# connector-top-j4-0.net
KiCad netlist of a schematic drawn in Altium Designer
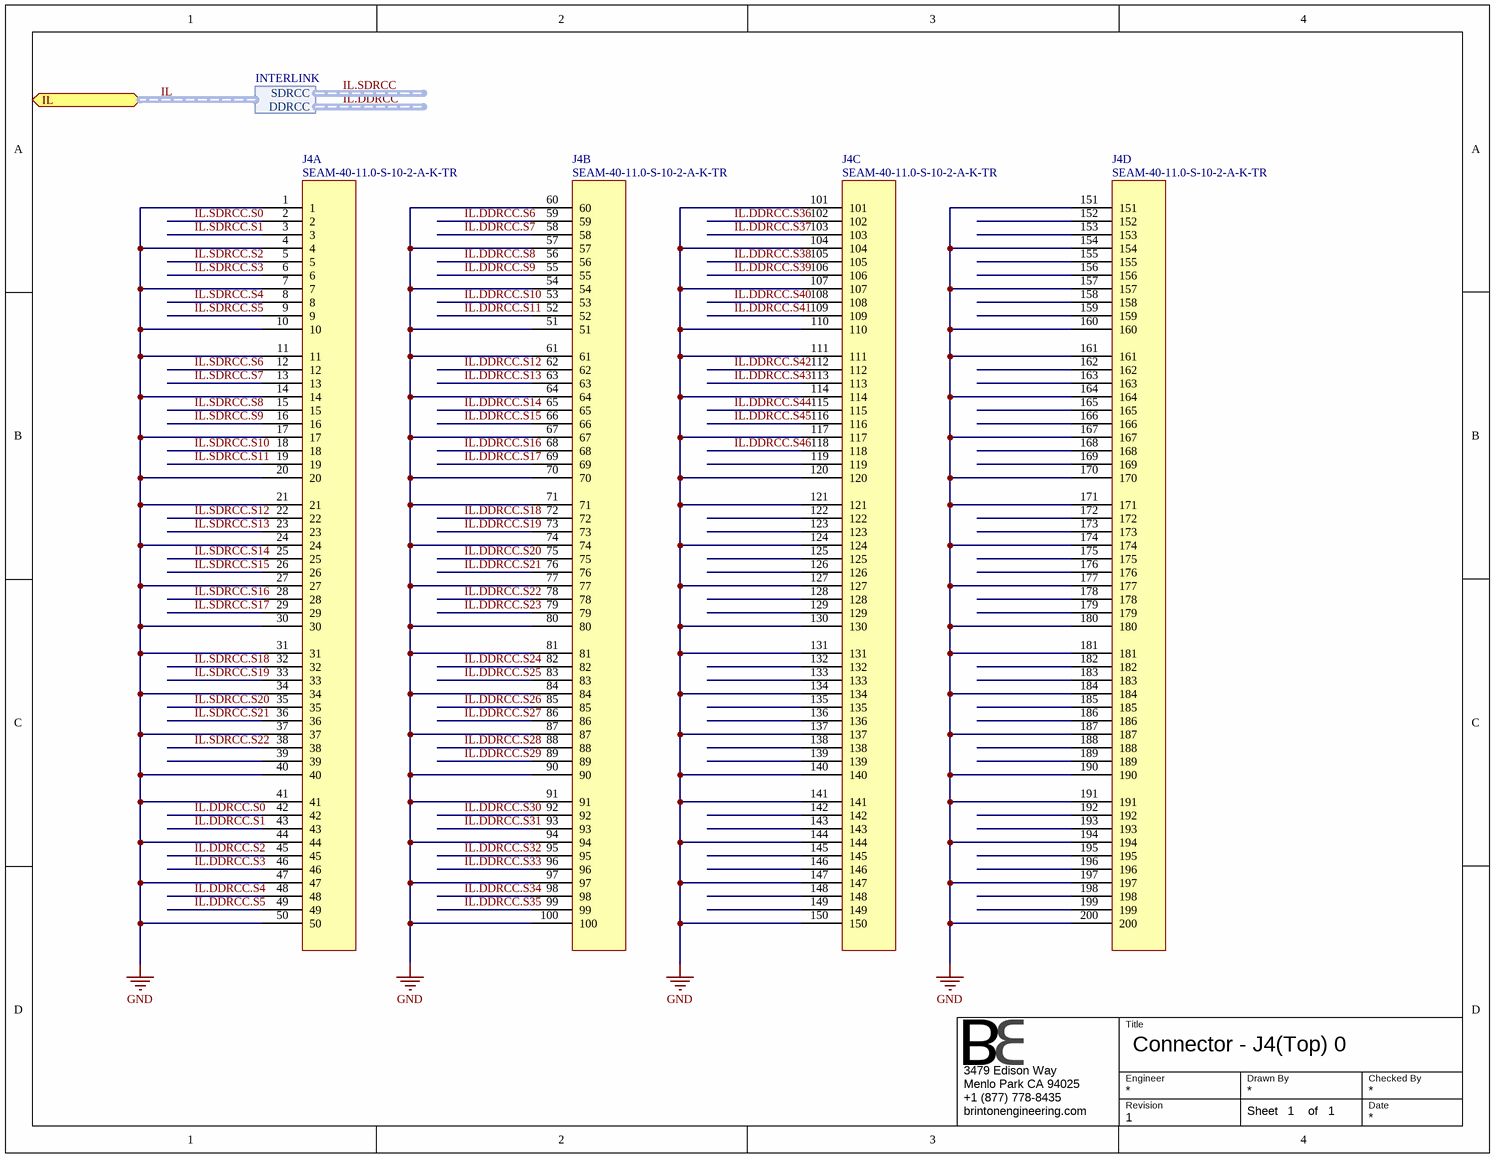
[diagram p0: connector-top-j4-0.SchDoc]

(export (version "E")
  (design (tool "Eeschema 10.0.6"))
  (components
    (comp (ref "J4")
      (value "SEAM-40-11.0-S-10-2-A-K-TR")
      (footprint "samtec:SEAM-40-11.0-S-10-2-A-K-TR")
      (description "Terminal Array Assembly, Surface Mount, 0.050\" Pitch, 400 Pins")
      (fields (field (name "MANUFACTURER") "Samtec"))
      (libsource (lib "samtec") (part "SEAM-40-11.0-S-10-2-A-K-TR"))
    )
  )
  (nets
    (net (code "3") (name "/IL.DDRCC.S0") (class "Default")
      (node (ref "J4") (pin "42") (pinfunction "42_42") (pintype "passive"))
    )
    (net (code "4") (name "/IL.DDRCC.S1") (class "Default")
      (node (ref "J4") (pin "43") (pinfunction "43_43") (pintype "passive"))
    )
    (net (code "5") (name "/IL.DDRCC.S2") (class "Default")
      (node (ref "J4") (pin "45") (pinfunction "45_45") (pintype "passive"))
    )
    (net (code "6") (name "/IL.DDRCC.S3") (class "Default")
      (node (ref "J4") (pin "46") (pinfunction "46_46") (pintype "passive"))
    )
    (net (code "7") (name "/IL.DDRCC.S4") (class "Default")
      (node (ref "J4") (pin "48") (pinfunction "48_48") (pintype "passive"))
    )
    (net (code "8") (name "/IL.DDRCC.S5") (class "Default")
      (node (ref "J4") (pin "49") (pinfunction "49_49") (pintype "passive"))
    )
    (net (code "9") (name "/IL.DDRCC.S6") (class "Default")
      (node (ref "J4") (pin "59") (pinfunction "59_59") (pintype "passive"))
    )
    (net (code "10") (name "/IL.DDRCC.S7") (class "Default")
      (node (ref "J4") (pin "58") (pinfunction "58_58") (pintype "passive"))
    )
    (net (code "11") (name "/IL.DDRCC.S8") (class "Default")
      (node (ref "J4") (pin "56") (pinfunction "56_56") (pintype "passive"))
    )
    (net (code "12") (name "/IL.DDRCC.S9") (class "Default")
      (node (ref "J4") (pin "55") (pinfunction "55_55") (pintype "passive"))
    )
    (net (code "13") (name "/IL.DDRCC.S10") (class "Default")
      (node (ref "J4") (pin "53") (pinfunction "53_53") (pintype "passive"))
    )
    (net (code "14") (name "/IL.DDRCC.S11") (class "Default")
      (node (ref "J4") (pin "52") (pinfunction "52_52") (pintype "passive"))
    )
    (net (code "15") (name "/IL.DDRCC.S12") (class "Default")
      (node (ref "J4") (pin "62") (pinfunction "62_62") (pintype "passive"))
    )
    (net (code "16") (name "/IL.DDRCC.S13") (class "Default")
      (node (ref "J4") (pin "63") (pinfunction "63_63") (pintype "passive"))
    )
    (net (code "17") (name "/IL.DDRCC.S14") (class "Default")
      (node (ref "J4") (pin "65") (pinfunction "65_65") (pintype "passive"))
    )
    (net (code "18") (name "/IL.DDRCC.S15") (class "Default")
      (node (ref "J4") (pin "66") (pinfunction "66_66") (pintype "passive"))
    )
    (net (code "19") (name "/IL.DDRCC.S16") (class "Default")
      (node (ref "J4") (pin "68") (pinfunction "68_68") (pintype "passive"))
    )
    (net (code "20") (name "/IL.DDRCC.S17") (class "Default")
      (node (ref "J4") (pin "69") (pinfunction "69_69") (pintype "passive"))
    )
    (net (code "21") (name "/IL.DDRCC.S18") (class "Default")
      (node (ref "J4") (pin "72") (pinfunction "72_72") (pintype "passive"))
    )
    (net (code "22") (name "/IL.DDRCC.S19") (class "Default")
      (node (ref "J4") (pin "73") (pinfunction "73_73") (pintype "passive"))
    )
    (net (code "23") (name "/IL.DDRCC.S20") (class "Default")
      (node (ref "J4") (pin "75") (pinfunction "75_75") (pintype "passive"))
    )
    (net (code "24") (name "/IL.DDRCC.S21") (class "Default")
      (node (ref "J4") (pin "76") (pinfunction "76_76") (pintype "passive"))
    )
    (net (code "25") (name "/IL.DDRCC.S22") (class "Default")
      (node (ref "J4") (pin "78") (pinfunction "78_78") (pintype "passive"))
    )
    (net (code "26") (name "/IL.DDRCC.S23") (class "Default")
      (node (ref "J4") (pin "79") (pinfunction "79_79") (pintype "passive"))
    )
    (net (code "27") (name "/IL.DDRCC.S24") (class "Default")
      (node (ref "J4") (pin "82") (pinfunction "82_82") (pintype "passive"))
    )
    (net (code "28") (name "/IL.DDRCC.S25") (class "Default")
      (node (ref "J4") (pin "83") (pinfunction "83_83") (pintype "passive"))
    )
    (net (code "29") (name "/IL.DDRCC.S26") (class "Default")
      (node (ref "J4") (pin "85") (pinfunction "85_85") (pintype "passive"))
    )
    (net (code "30") (name "/IL.DDRCC.S27") (class "Default")
      (node (ref "J4") (pin "86") (pinfunction "86_86") (pintype "passive"))
    )
    (net (code "31") (name "/IL.DDRCC.S28") (class "Default")
      (node (ref "J4") (pin "88") (pinfunction "88_88") (pintype "passive"))
    )
    (net (code "32") (name "/IL.DDRCC.S29") (class "Default")
      (node (ref "J4") (pin "89") (pinfunction "89_89") (pintype "passive"))
    )
    (net (code "33") (name "/IL.DDRCC.S30") (class "Default")
      (node (ref "J4") (pin "92") (pinfunction "92_92") (pintype "passive"))
    )
    (net (code "34") (name "/IL.DDRCC.S31") (class "Default")
      (node (ref "J4") (pin "93") (pinfunction "93_93") (pintype "passive"))
    )
    (net (code "35") (name "/IL.DDRCC.S32") (class "Default")
      (node (ref "J4") (pin "95") (pinfunction "95_95") (pintype "passive"))
    )
    (net (code "36") (name "/IL.DDRCC.S33") (class "Default")
      (node (ref "J4") (pin "96") (pinfunction "96_96") (pintype "passive"))
    )
    (net (code "37") (name "/IL.DDRCC.S34") (class "Default")
      (node (ref "J4") (pin "98") (pinfunction "98_98") (pintype "passive"))
    )
    (net (code "38") (name "/IL.DDRCC.S35") (class "Default")
      (node (ref "J4") (pin "99") (pinfunction "99_99") (pintype "passive"))
    )
    (net (code "39") (name "/IL.DDRCC.S36") (class "Default")
      (node (ref "J4") (pin "102") (pinfunction "102_102") (pintype "passive"))
    )
    (net (code "40") (name "/IL.DDRCC.S37") (class "Default")
      (node (ref "J4") (pin "103") (pinfunction "103_103") (pintype "passive"))
    )
    (net (code "41") (name "/IL.DDRCC.S38") (class "Default")
      (node (ref "J4") (pin "105") (pinfunction "105_105") (pintype "passive"))
    )
    (net (code "42") (name "/IL.DDRCC.S39") (class "Default")
      (node (ref "J4") (pin "106") (pinfunction "106_106") (pintype "passive"))
    )
    (net (code "43") (name "/IL.DDRCC.S40") (class "Default")
      (node (ref "J4") (pin "108") (pinfunction "108_108") (pintype "passive"))
    )
    (net (code "44") (name "/IL.DDRCC.S41") (class "Default")
      (node (ref "J4") (pin "109") (pinfunction "109_109") (pintype "passive"))
    )
    (net (code "45") (name "/IL.DDRCC.S42") (class "Default")
      (node (ref "J4") (pin "112") (pinfunction "112_112") (pintype "passive"))
    )
    (net (code "46") (name "/IL.DDRCC.S43") (class "Default")
      (node (ref "J4") (pin "113") (pinfunction "113_113") (pintype "passive"))
    )
    (net (code "47") (name "/IL.DDRCC.S44") (class "Default")
      (node (ref "J4") (pin "115") (pinfunction "115_115") (pintype "passive"))
    )
    (net (code "48") (name "/IL.DDRCC.S45") (class "Default")
      (node (ref "J4") (pin "116") (pinfunction "116_116") (pintype "passive"))
    )
    (net (code "49") (name "/IL.DDRCC.S46") (class "Default")
      (node (ref "J4") (pin "118") (pinfunction "118_118") (pintype "passive"))
    )
    (net (code "51") (name "/IL.SDRCC.S0") (class "Default")
      (node (ref "J4") (pin "2") (pinfunction "2_2") (pintype "passive"))
    )
    (net (code "52") (name "/IL.SDRCC.S1") (class "Default")
      (node (ref "J4") (pin "3") (pinfunction "3_3") (pintype "passive"))
    )
    (net (code "53") (name "/IL.SDRCC.S2") (class "Default")
      (node (ref "J4") (pin "5") (pinfunction "5_5") (pintype "passive"))
    )
    (net (code "54") (name "/IL.SDRCC.S3") (class "Default")
      (node (ref "J4") (pin "6") (pinfunction "6_6") (pintype "passive"))
    )
    (net (code "55") (name "/IL.SDRCC.S4") (class "Default")
      (node (ref "J4") (pin "8") (pinfunction "8_8") (pintype "passive"))
    )
    (net (code "56") (name "/IL.SDRCC.S5") (class "Default")
      (node (ref "J4") (pin "9") (pinfunction "9_9") (pintype "passive"))
    )
    (net (code "57") (name "/IL.SDRCC.S6") (class "Default")
      (node (ref "J4") (pin "12") (pinfunction "12_12") (pintype "passive"))
    )
    (net (code "58") (name "/IL.SDRCC.S7") (class "Default")
      (node (ref "J4") (pin "13") (pinfunction "13_13") (pintype "passive"))
    )
    (net (code "59") (name "/IL.SDRCC.S8") (class "Default")
      (node (ref "J4") (pin "15") (pinfunction "15_15") (pintype "passive"))
    )
    (net (code "60") (name "/IL.SDRCC.S9") (class "Default")
      (node (ref "J4") (pin "16") (pinfunction "16_16") (pintype "passive"))
    )
    (net (code "61") (name "/IL.SDRCC.S10") (class "Default")
      (node (ref "J4") (pin "18") (pinfunction "18_18") (pintype "passive"))
    )
    (net (code "62") (name "/IL.SDRCC.S11") (class "Default")
      (node (ref "J4") (pin "19") (pinfunction "19_19") (pintype "passive"))
    )
    (net (code "63") (name "/IL.SDRCC.S12") (class "Default")
      (node (ref "J4") (pin "22") (pinfunction "22_22") (pintype "passive"))
    )
    (net (code "64") (name "/IL.SDRCC.S13") (class "Default")
      (node (ref "J4") (pin "23") (pinfunction "23_23") (pintype "passive"))
    )
    (net (code "65") (name "/IL.SDRCC.S14") (class "Default")
      (node (ref "J4") (pin "25") (pinfunction "25_25") (pintype "passive"))
    )
    (net (code "66") (name "/IL.SDRCC.S15") (class "Default")
      (node (ref "J4") (pin "26") (pinfunction "26_26") (pintype "passive"))
    )
    (net (code "67") (name "/IL.SDRCC.S16") (class "Default")
      (node (ref "J4") (pin "28") (pinfunction "28_28") (pintype "passive"))
    )
    (net (code "68") (name "/IL.SDRCC.S17") (class "Default")
      (node (ref "J4") (pin "29") (pinfunction "29_29") (pintype "passive"))
    )
    (net (code "69") (name "/IL.SDRCC.S18") (class "Default")
      (node (ref "J4") (pin "32") (pinfunction "32_32") (pintype "passive"))
    )
    (net (code "70") (name "/IL.SDRCC.S19") (class "Default")
      (node (ref "J4") (pin "33") (pinfunction "33_33") (pintype "passive"))
    )
    (net (code "71") (name "/IL.SDRCC.S20") (class "Default")
      (node (ref "J4") (pin "35") (pinfunction "35_35") (pintype "passive"))
    )
    (net (code "72") (name "/IL.SDRCC.S21") (class "Default")
      (node (ref "J4") (pin "36") (pinfunction "36_36") (pintype "passive"))
    )
    (net (code "73") (name "/IL.SDRCC.S22") (class "Default")
      (node (ref "J4") (pin "38") (pinfunction "38_38") (pintype "passive"))
    )
    (net (code "75") (name "GND") (class "Default")
      (node (ref "J4") (pin "1") (pinfunction "1_1") (pintype "passive"))
      (node (ref "J4") (pin "10") (pinfunction "10_10") (pintype "passive"))
      (node (ref "J4") (pin "100") (pinfunction "100_100") (pintype "passive"))
      (node (ref "J4") (pin "101") (pinfunction "101_101") (pintype "passive"))
      (node (ref "J4") (pin "104") (pinfunction "104_104") (pintype "passive"))
      (node (ref "J4") (pin "107") (pinfunction "107_107") (pintype "passive"))
      (node (ref "J4") (pin "11") (pinfunction "11_11") (pintype "passive"))
      (node (ref "J4") (pin "110") (pinfunction "110_110") (pintype "passive"))
      (node (ref "J4") (pin "111") (pinfunction "111_111") (pintype "passive"))
      (node (ref "J4") (pin "114") (pinfunction "114_114") (pintype "passive"))
      (node (ref "J4") (pin "117") (pinfunction "117_117") (pintype "passive"))
      (node (ref "J4") (pin "120") (pinfunction "120_120") (pintype "passive"))
      (node (ref "J4") (pin "121") (pinfunction "121_121") (pintype "passive"))
      (node (ref "J4") (pin "124") (pinfunction "124_124") (pintype "passive"))
      (node (ref "J4") (pin "127") (pinfunction "127_127") (pintype "passive"))
      (node (ref "J4") (pin "130") (pinfunction "130_130") (pintype "passive"))
      (node (ref "J4") (pin "131") (pinfunction "131_131") (pintype "passive"))
      (node (ref "J4") (pin "134") (pinfunction "134_134") (pintype "passive"))
      (node (ref "J4") (pin "137") (pinfunction "137_137") (pintype "passive"))
      (node (ref "J4") (pin "14") (pinfunction "14_14") (pintype "passive"))
      (node (ref "J4") (pin "140") (pinfunction "140_140") (pintype "passive"))
      (node (ref "J4") (pin "141") (pinfunction "141_141") (pintype "passive"))
      (node (ref "J4") (pin "144") (pinfunction "144_144") (pintype "passive"))
      (node (ref "J4") (pin "147") (pinfunction "147_147") (pintype "passive"))
      (node (ref "J4") (pin "150") (pinfunction "150_150") (pintype "passive"))
      (node (ref "J4") (pin "151") (pinfunction "151_151") (pintype "passive"))
      (node (ref "J4") (pin "154") (pinfunction "154_154") (pintype "passive"))
      (node (ref "J4") (pin "157") (pinfunction "157_157") (pintype "passive"))
      (node (ref "J4") (pin "160") (pinfunction "160_160") (pintype "passive"))
      (node (ref "J4") (pin "161") (pinfunction "161_161") (pintype "passive"))
      (node (ref "J4") (pin "164") (pinfunction "164_164") (pintype "passive"))
      (node (ref "J4") (pin "167") (pinfunction "167_167") (pintype "passive"))
      (node (ref "J4") (pin "17") (pinfunction "17_17") (pintype "passive"))
      (node (ref "J4") (pin "170") (pinfunction "170_170") (pintype "passive"))
      (node (ref "J4") (pin "171") (pinfunction "171_171") (pintype "passive"))
      (node (ref "J4") (pin "174") (pinfunction "174_174") (pintype "passive"))
      (node (ref "J4") (pin "177") (pinfunction "177_177") (pintype "passive"))
      (node (ref "J4") (pin "180") (pinfunction "180_180") (pintype "passive"))
      (node (ref "J4") (pin "181") (pinfunction "181_181") (pintype "passive"))
      (node (ref "J4") (pin "184") (pinfunction "184_184") (pintype "passive"))
      (node (ref "J4") (pin "187") (pinfunction "187_187") (pintype "passive"))
      (node (ref "J4") (pin "190") (pinfunction "190_190") (pintype "passive"))
      (node (ref "J4") (pin "191") (pinfunction "191_191") (pintype "passive"))
      (node (ref "J4") (pin "194") (pinfunction "194_194") (pintype "passive"))
      (node (ref "J4") (pin "197") (pinfunction "197_197") (pintype "passive"))
      (node (ref "J4") (pin "20") (pinfunction "20_20") (pintype "passive"))
      (node (ref "J4") (pin "200") (pinfunction "200_200") (pintype "passive"))
      (node (ref "J4") (pin "21") (pinfunction "21_21") (pintype "passive"))
      (node (ref "J4") (pin "24") (pinfunction "24_24") (pintype "passive"))
      (node (ref "J4") (pin "27") (pinfunction "27_27") (pintype "passive"))
      (node (ref "J4") (pin "30") (pinfunction "30_30") (pintype "passive"))
      (node (ref "J4") (pin "31") (pinfunction "31_31") (pintype "passive"))
      (node (ref "J4") (pin "34") (pinfunction "34_34") (pintype "passive"))
      (node (ref "J4") (pin "37") (pinfunction "37_37") (pintype "passive"))
      (node (ref "J4") (pin "4") (pinfunction "4_4") (pintype "passive"))
      (node (ref "J4") (pin "40") (pinfunction "40_40") (pintype "passive"))
      (node (ref "J4") (pin "41") (pinfunction "41_41") (pintype "passive"))
      (node (ref "J4") (pin "44") (pinfunction "44_44") (pintype "passive"))
      (node (ref "J4") (pin "47") (pinfunction "47_47") (pintype "passive"))
      (node (ref "J4") (pin "50") (pinfunction "50_50") (pintype "passive"))
      (node (ref "J4") (pin "51") (pinfunction "51_51") (pintype "passive"))
      (node (ref "J4") (pin "54") (pinfunction "54_54") (pintype "passive"))
      (node (ref "J4") (pin "57") (pinfunction "57_57") (pintype "passive"))
      (node (ref "J4") (pin "60") (pinfunction "60_60") (pintype "passive"))
      (node (ref "J4") (pin "61") (pinfunction "61_61") (pintype "passive"))
      (node (ref "J4") (pin "64") (pinfunction "64_64") (pintype "passive"))
      (node (ref "J4") (pin "67") (pinfunction "67_67") (pintype "passive"))
      (node (ref "J4") (pin "7") (pinfunction "7_7") (pintype "passive"))
      (node (ref "J4") (pin "70") (pinfunction "70_70") (pintype "passive"))
      (node (ref "J4") (pin "71") (pinfunction "71_71") (pintype "passive"))
      (node (ref "J4") (pin "74") (pinfunction "74_74") (pintype "passive"))
      (node (ref "J4") (pin "77") (pinfunction "77_77") (pintype "passive"))
      (node (ref "J4") (pin "80") (pinfunction "80_80") (pintype "passive"))
      (node (ref "J4") (pin "81") (pinfunction "81_81") (pintype "passive"))
      (node (ref "J4") (pin "84") (pinfunction "84_84") (pintype "passive"))
      (node (ref "J4") (pin "87") (pinfunction "87_87") (pintype "passive"))
      (node (ref "J4") (pin "90") (pinfunction "90_90") (pintype "passive"))
      (node (ref "J4") (pin "91") (pinfunction "91_91") (pintype "passive"))
      (node (ref "J4") (pin "94") (pinfunction "94_94") (pintype "passive"))
      (node (ref "J4") (pin "97") (pinfunction "97_97") (pintype "passive"))
    )
    (net (code "76") (name "unconnected-(J4-Pad39)") (class "Default")
      (node (ref "J4") (pin "39") (pinfunction "39_39") (pintype "passive"))
    )
    (net (code "77") (name "unconnected-(J4-Pad119)") (class "Default")
      (node (ref "J4") (pin "119") (pinfunction "119_119") (pintype "passive"))
    )
    (net (code "78") (name "unconnected-(J4-Pad122)") (class "Default")
      (node (ref "J4") (pin "122") (pinfunction "122_122") (pintype "passive"))
    )
    (net (code "79") (name "unconnected-(J4-Pad123)") (class "Default")
      (node (ref "J4") (pin "123") (pinfunction "123_123") (pintype "passive"))
    )
    (net (code "80") (name "unconnected-(J4-Pad125)") (class "Default")
      (node (ref "J4") (pin "125") (pinfunction "125_125") (pintype "passive"))
    )
    (net (code "81") (name "unconnected-(J4-Pad126)") (class "Default")
      (node (ref "J4") (pin "126") (pinfunction "126_126") (pintype "passive"))
    )
    (net (code "82") (name "unconnected-(J4-Pad128)") (class "Default")
      (node (ref "J4") (pin "128") (pinfunction "128_128") (pintype "passive"))
    )
    (net (code "83") (name "unconnected-(J4-Pad129)") (class "Default")
      (node (ref "J4") (pin "129") (pinfunction "129_129") (pintype "passive"))
    )
    (net (code "84") (name "unconnected-(J4-Pad132)") (class "Default")
      (node (ref "J4") (pin "132") (pinfunction "132_132") (pintype "passive"))
    )
    (net (code "85") (name "unconnected-(J4-Pad133)") (class "Default")
      (node (ref "J4") (pin "133") (pinfunction "133_133") (pintype "passive"))
    )
    (net (code "86") (name "unconnected-(J4-Pad135)") (class "Default")
      (node (ref "J4") (pin "135") (pinfunction "135_135") (pintype "passive"))
    )
    (net (code "87") (name "unconnected-(J4-Pad136)") (class "Default")
      (node (ref "J4") (pin "136") (pinfunction "136_136") (pintype "passive"))
    )
    (net (code "88") (name "unconnected-(J4-Pad138)") (class "Default")
      (node (ref "J4") (pin "138") (pinfunction "138_138") (pintype "passive"))
    )
    (net (code "89") (name "unconnected-(J4-Pad139)") (class "Default")
      (node (ref "J4") (pin "139") (pinfunction "139_139") (pintype "passive"))
    )
    (net (code "90") (name "unconnected-(J4-Pad142)") (class "Default")
      (node (ref "J4") (pin "142") (pinfunction "142_142") (pintype "passive"))
    )
    (net (code "91") (name "unconnected-(J4-Pad143)") (class "Default")
      (node (ref "J4") (pin "143") (pinfunction "143_143") (pintype "passive"))
    )
    (net (code "92") (name "unconnected-(J4-Pad145)") (class "Default")
      (node (ref "J4") (pin "145") (pinfunction "145_145") (pintype "passive"))
    )
    (net (code "93") (name "unconnected-(J4-Pad146)") (class "Default")
      (node (ref "J4") (pin "146") (pinfunction "146_146") (pintype "passive"))
    )
    (net (code "94") (name "unconnected-(J4-Pad148)") (class "Default")
      (node (ref "J4") (pin "148") (pinfunction "148_148") (pintype "passive"))
    )
    (net (code "95") (name "unconnected-(J4-Pad149)") (class "Default")
      (node (ref "J4") (pin "149") (pinfunction "149_149") (pintype "passive"))
    )
    (net (code "96") (name "unconnected-(J4-Pad152)") (class "Default")
      (node (ref "J4") (pin "152") (pinfunction "152_152") (pintype "passive"))
    )
    (net (code "97") (name "unconnected-(J4-Pad153)") (class "Default")
      (node (ref "J4") (pin "153") (pinfunction "153_153") (pintype "passive"))
    )
    (net (code "98") (name "unconnected-(J4-Pad155)") (class "Default")
      (node (ref "J4") (pin "155") (pinfunction "155_155") (pintype "passive"))
    )
    (net (code "99") (name "unconnected-(J4-Pad156)") (class "Default")
      (node (ref "J4") (pin "156") (pinfunction "156_156") (pintype "passive"))
    )
    (net (code "100") (name "unconnected-(J4-Pad158)") (class "Default")
      (node (ref "J4") (pin "158") (pinfunction "158_158") (pintype "passive"))
    )
    (net (code "101") (name "unconnected-(J4-Pad159)") (class "Default")
      (node (ref "J4") (pin "159") (pinfunction "159_159") (pintype "passive"))
    )
    (net (code "102") (name "unconnected-(J4-Pad162)") (class "Default")
      (node (ref "J4") (pin "162") (pinfunction "162_162") (pintype "passive"))
    )
    (net (code "103") (name "unconnected-(J4-Pad163)") (class "Default")
      (node (ref "J4") (pin "163") (pinfunction "163_163") (pintype "passive"))
    )
    (net (code "104") (name "unconnected-(J4-Pad165)") (class "Default")
      (node (ref "J4") (pin "165") (pinfunction "165_165") (pintype "passive"))
    )
    (net (code "105") (name "unconnected-(J4-Pad166)") (class "Default")
      (node (ref "J4") (pin "166") (pinfunction "166_166") (pintype "passive"))
    )
    (net (code "106") (name "unconnected-(J4-Pad168)") (class "Default")
      (node (ref "J4") (pin "168") (pinfunction "168_168") (pintype "passive"))
    )
    (net (code "107") (name "unconnected-(J4-Pad169)") (class "Default")
      (node (ref "J4") (pin "169") (pinfunction "169_169") (pintype "passive"))
    )
    (net (code "108") (name "unconnected-(J4-Pad172)") (class "Default")
      (node (ref "J4") (pin "172") (pinfunction "172_172") (pintype "passive"))
    )
    (net (code "109") (name "unconnected-(J4-Pad173)") (class "Default")
      (node (ref "J4") (pin "173") (pinfunction "173_173") (pintype "passive"))
    )
    (net (code "110") (name "unconnected-(J4-Pad175)") (class "Default")
      (node (ref "J4") (pin "175") (pinfunction "175_175") (pintype "passive"))
    )
    (net (code "111") (name "unconnected-(J4-Pad176)") (class "Default")
      (node (ref "J4") (pin "176") (pinfunction "176_176") (pintype "passive"))
    )
    (net (code "112") (name "unconnected-(J4-Pad178)") (class "Default")
      (node (ref "J4") (pin "178") (pinfunction "178_178") (pintype "passive"))
    )
    (net (code "113") (name "unconnected-(J4-Pad179)") (class "Default")
      (node (ref "J4") (pin "179") (pinfunction "179_179") (pintype "passive"))
    )
    (net (code "114") (name "unconnected-(J4-Pad182)") (class "Default")
      (node (ref "J4") (pin "182") (pinfunction "182_182") (pintype "passive"))
    )
    (net (code "115") (name "unconnected-(J4-Pad183)") (class "Default")
      (node (ref "J4") (pin "183") (pinfunction "183_183") (pintype "passive"))
    )
    (net (code "116") (name "unconnected-(J4-Pad185)") (class "Default")
      (node (ref "J4") (pin "185") (pinfunction "185_185") (pintype "passive"))
    )
    (net (code "117") (name "unconnected-(J4-Pad186)") (class "Default")
      (node (ref "J4") (pin "186") (pinfunction "186_186") (pintype "passive"))
    )
    (net (code "118") (name "unconnected-(J4-Pad188)") (class "Default")
      (node (ref "J4") (pin "188") (pinfunction "188_188") (pintype "passive"))
    )
    (net (code "119") (name "unconnected-(J4-Pad189)") (class "Default")
      (node (ref "J4") (pin "189") (pinfunction "189_189") (pintype "passive"))
    )
    (net (code "120") (name "unconnected-(J4-Pad192)") (class "Default")
      (node (ref "J4") (pin "192") (pinfunction "192_192") (pintype "passive"))
    )
    (net (code "121") (name "unconnected-(J4-Pad193)") (class "Default")
      (node (ref "J4") (pin "193") (pinfunction "193_193") (pintype "passive"))
    )
    (net (code "122") (name "unconnected-(J4-Pad195)") (class "Default")
      (node (ref "J4") (pin "195") (pinfunction "195_195") (pintype "passive"))
    )
    (net (code "123") (name "unconnected-(J4-Pad196)") (class "Default")
      (node (ref "J4") (pin "196") (pinfunction "196_196") (pintype "passive"))
    )
    (net (code "124") (name "unconnected-(J4-Pad198)") (class "Default")
      (node (ref "J4") (pin "198") (pinfunction "198_198") (pintype "passive"))
    )
    (net (code "125") (name "unconnected-(J4-Pad199)") (class "Default")
      (node (ref "J4") (pin "199") (pinfunction "199_199") (pintype "passive"))
    )
  )
)
